# proiect-tsc.net
KiCad netlist of a schematic drawn in EAGLE
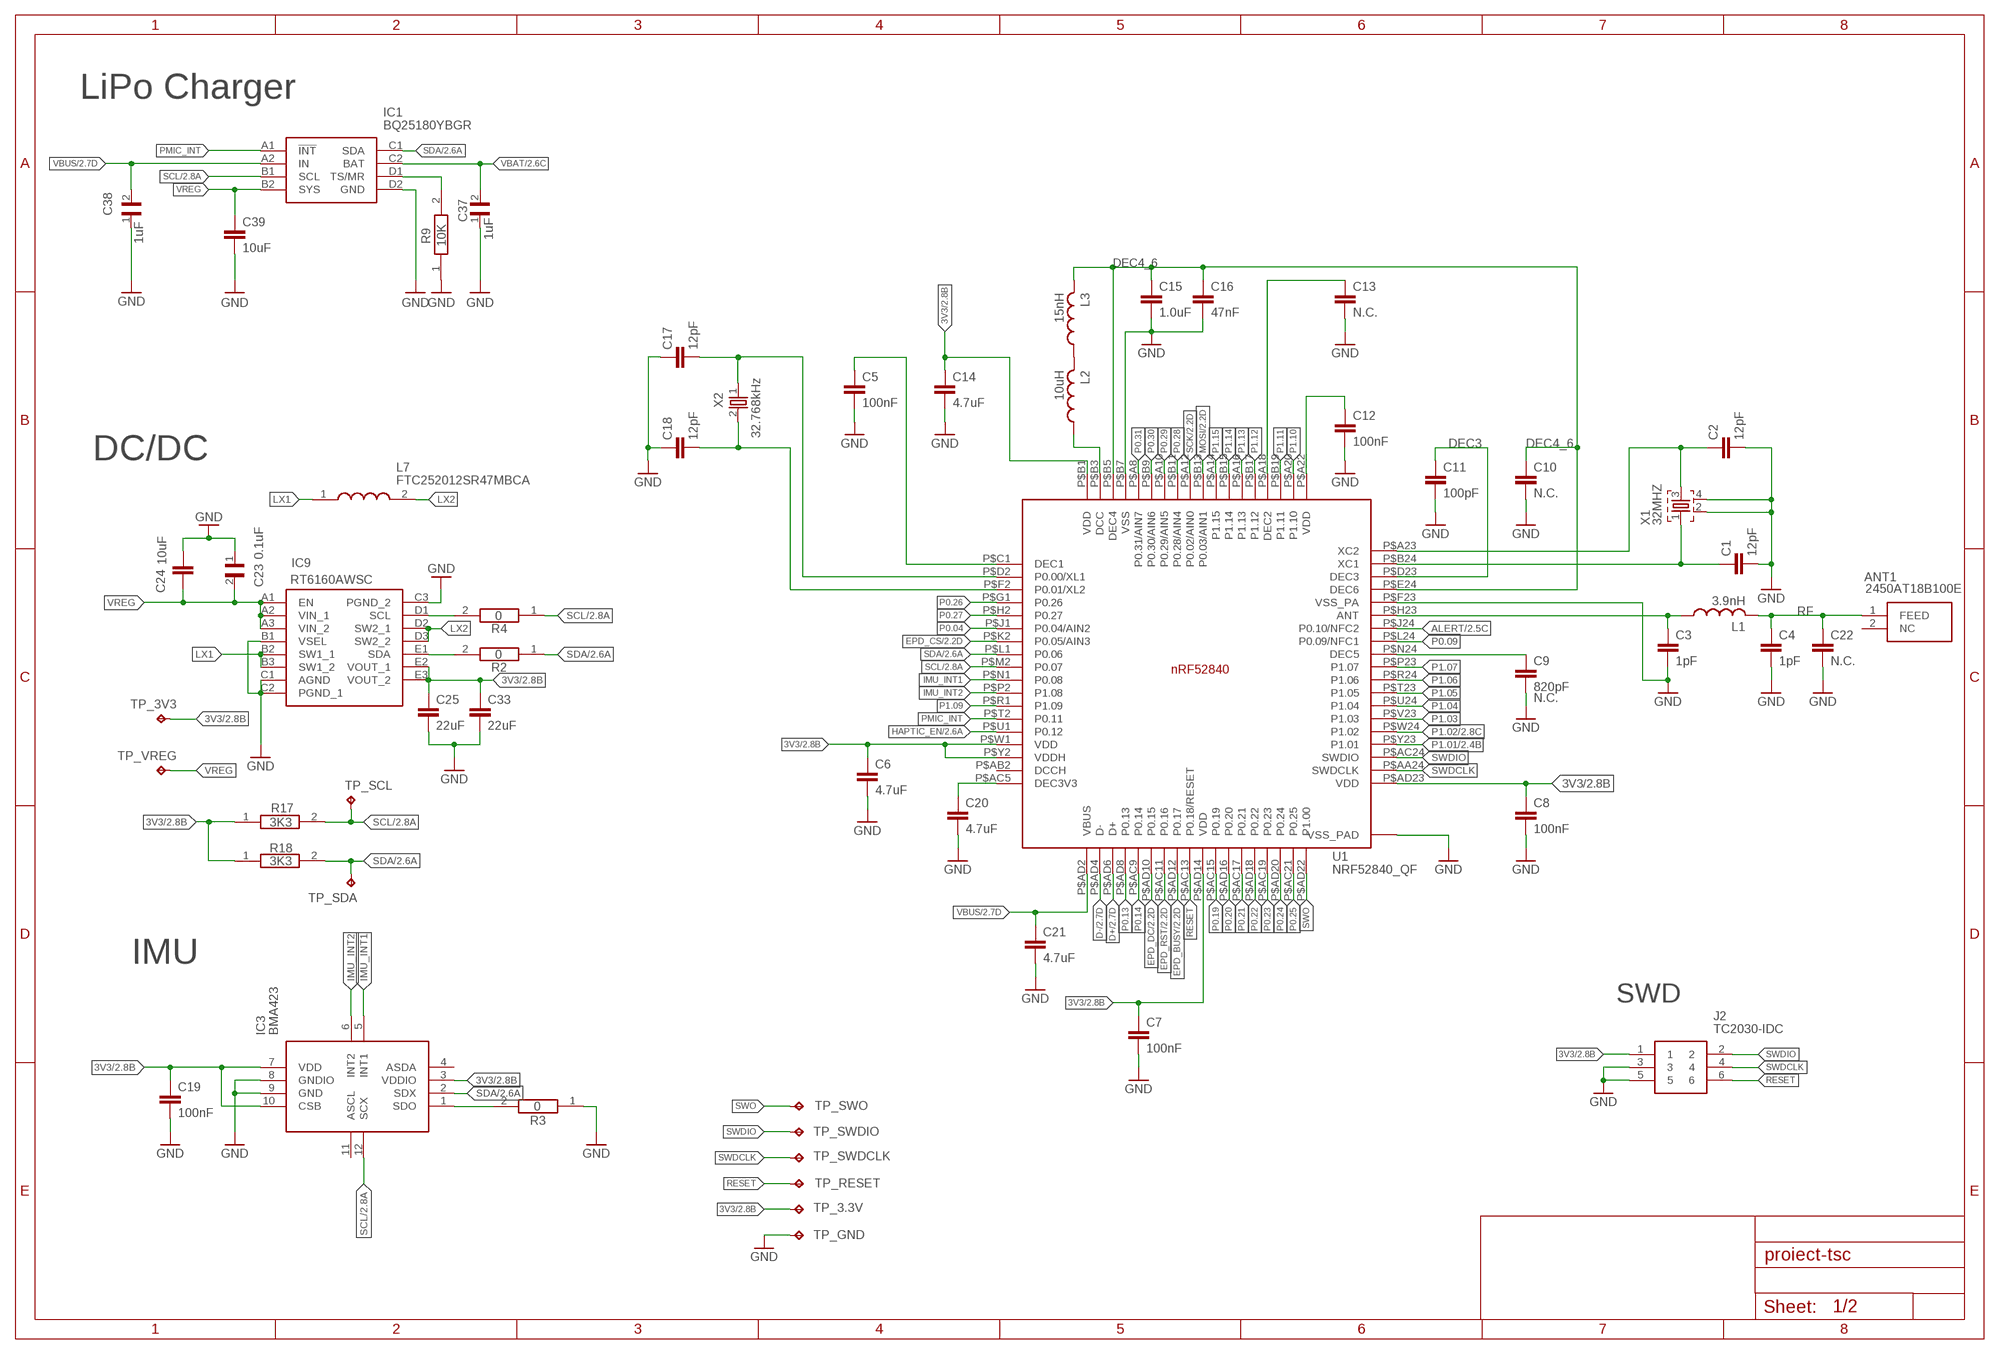
[diagram p0: schematic, sheet 1]
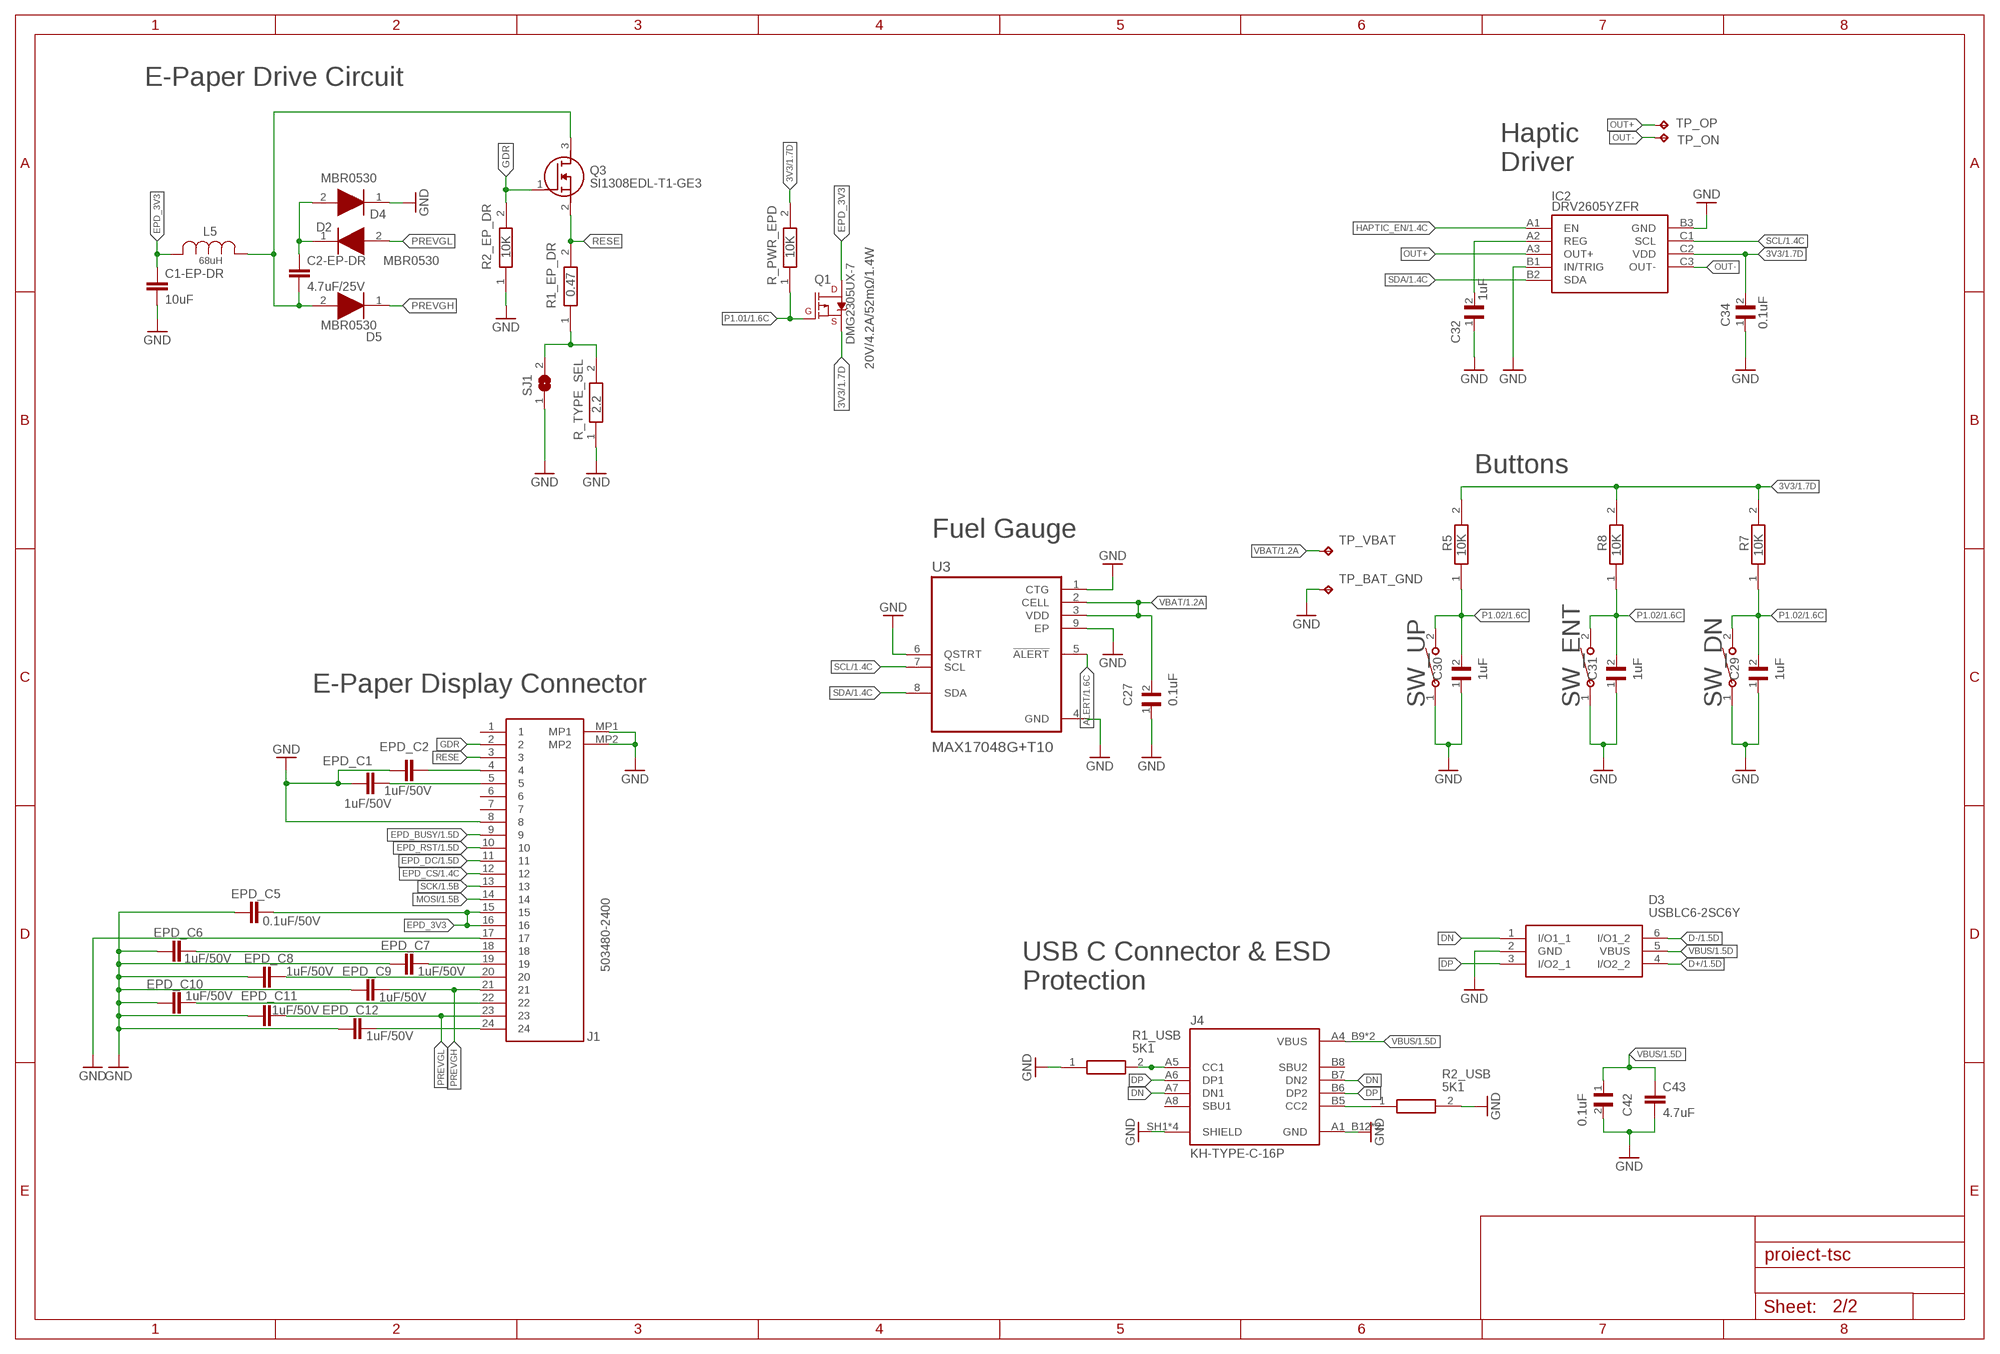
[diagram p1: schematic, sheet 2]

(export (version "E")
  (design (tool "Eeschema 10.0.6"))
  (components
    (comp (ref "C1-EP-DR")
      (value "10uF")
      (footprint "eagle-import:NORDIC_NRF_3_RESC0402_L")
      (libsource (lib "eagle-import") (part "NORDIC_NRF_3_CAPACITOR_0402_L"))
    )
    (comp (ref "C2-EP-DR")
      (value "4.7uF/25V")
      (footprint "eagle-import:NORDIC_NRF_3_RESC0402_L")
      (libsource (lib "eagle-import") (part "NORDIC_NRF_3_CAPACITOR_0402_L"))
    )
    (comp (ref "C27")
      (value "0.1uF")
      (footprint "eagle-import:GRM011R60J152KE01L_2_CAPC0201X13N")
      (fields (field (name "MF") "Murata") (field (name "MP") "GRM011R60J152KE01L"))
      (libsource (lib "eagle-import") (part "GRM011R60J152KE01L_2_GRM011R60J152KE01L"))
    )
    (comp (ref "C29")
      (value "1uF")
      (footprint "eagle-import:GRM011R60J152KE01L_1_0201")
      (libsource (lib "eagle-import") (part "GRM011R60J152KE01L_1_GRM011R60J152KE01L"))
    )
    (comp (ref "C30")
      (value "1uF")
      (footprint "eagle-import:GRM011R60J152KE01L_1_0201")
      (libsource (lib "eagle-import") (part "GRM011R60J152KE01L_1_GRM011R60J152KE01L"))
    )
    (comp (ref "C31")
      (value "1uF")
      (footprint "eagle-import:GRM011R60J152KE01L_1_0201")
      (libsource (lib "eagle-import") (part "GRM011R60J152KE01L_1_GRM011R60J152KE01L"))
    )
    (comp (ref "C32")
      (value "1uF")
      (footprint "eagle-import:GRM011R60J152KE01L_2_CAPC0201X13N")
      (fields (field (name "MF") "Murata") (field (name "MP") "GRM011R60J152KE01L"))
      (libsource (lib "eagle-import") (part "GRM011R60J152KE01L_2_GRM011R60J152KE01L"))
    )
    (comp (ref "C34")
      (value "0.1uF")
      (footprint "eagle-import:GRM011R60J152KE01L_2_CAPC0201X13N")
      (fields (field (name "MF") "Murata") (field (name "MP") "GRM011R60J152KE01L"))
      (libsource (lib "eagle-import") (part "GRM011R60J152KE01L_2_GRM011R60J152KE01L"))
    )
    (comp (ref "C42")
      (value "0.1uF")
      (footprint "eagle-import:GRM011R60J152KE01L_1_0201")
      (libsource (lib "eagle-import") (part "GRM011R60J152KE01L_1_GRM011R60J152KE01L"))
    )
    (comp (ref "C43")
      (value "4.7uF")
      (footprint "eagle-import:PERFECT_0402_0402")
      (libsource (lib "eagle-import") (part "PERFECT_0402_CAP_0402"))
    )
    (comp (ref "D2")
      (value "MBR0530")
      (footprint "eagle-import:ESP32_C6_LIBRARY_5_SOD3716X135N")
      (fields (field (name "MF") "ON Semiconductor"))
      (libsource (lib "eagle-import") (part "ESP32_C6_LIBRARY_5_MBR0530"))
    )
    (comp (ref "D3")
      (value "USBLC6-2SC6Y")
      (footprint "eagle-import:ESP32_C6_LIBRARY_3_SOT95P280X145-6N")
      (fields (field (name "MF") "STMicroelectronics"))
      (libsource (lib "eagle-import") (part "ESP32_C6_LIBRARY_3_USBLC6-2SC6Y"))
    )
    (comp (ref "D4")
      (value "MBR0530")
      (footprint "eagle-import:ESP32_C6_LIBRARY_5_SOD3716X135N")
      (fields (field (name "MF") "ON Semiconductor"))
      (libsource (lib "eagle-import") (part "ESP32_C6_LIBRARY_5_MBR0530"))
    )
    (comp (ref "D5")
      (value "MBR0530")
      (footprint "eagle-import:ESP32_C6_LIBRARY_5_SOD3716X135N")
      (fields (field (name "MF") "ON Semiconductor"))
      (libsource (lib "eagle-import") (part "ESP32_C6_LIBRARY_5_MBR0530"))
    )
    (comp (ref "EPD_C1")
      (value "1uF/50V")
      (footprint "eagle-import:NORDIC_NRF_3_RESC0402_L")
      (libsource (lib "eagle-import") (part "NORDIC_NRF_3_CAPACITOR_0402_L"))
    )
    (comp (ref "EPD_C2")
      (value "1uF/50V")
      (footprint "eagle-import:NORDIC_NRF_3_RESC0402_L")
      (libsource (lib "eagle-import") (part "NORDIC_NRF_3_CAPACITOR_0402_L"))
    )
    (comp (ref "EPD_C5")
      (value "0.1uF/50V")
      (footprint "eagle-import:NORDIC_NRF_3_RESC0402_L")
      (libsource (lib "eagle-import") (part "NORDIC_NRF_3_CAPACITOR_0402_L"))
    )
    (comp (ref "EPD_C6")
      (value "1uF/50V")
      (footprint "eagle-import:NORDIC_NRF_3_RESC0402_L")
      (libsource (lib "eagle-import") (part "NORDIC_NRF_3_CAPACITOR_0402_L"))
    )
    (comp (ref "EPD_C7")
      (value "1uF/50V")
      (footprint "eagle-import:NORDIC_NRF_3_RESC0402_L")
      (libsource (lib "eagle-import") (part "NORDIC_NRF_3_CAPACITOR_0402_L"))
    )
    (comp (ref "EPD_C8")
      (value "1uF/50V")
      (footprint "eagle-import:NORDIC_NRF_3_RESC0402_L")
      (libsource (lib "eagle-import") (part "NORDIC_NRF_3_CAPACITOR_0402_L"))
    )
    (comp (ref "EPD_C9")
      (value "1uF/50V")
      (footprint "eagle-import:NORDIC_NRF_3_RESC0402_L")
      (libsource (lib "eagle-import") (part "NORDIC_NRF_3_CAPACITOR_0402_L"))
    )
    (comp (ref "EPD_C10")
      (value "1uF/50V")
      (footprint "eagle-import:NORDIC_NRF_3_RESC0402_L")
      (libsource (lib "eagle-import") (part "NORDIC_NRF_3_CAPACITOR_0402_L"))
    )
    (comp (ref "EPD_C11")
      (value "1uF/50V")
      (footprint "eagle-import:NORDIC_NRF_3_RESC0402_L")
      (libsource (lib "eagle-import") (part "NORDIC_NRF_3_CAPACITOR_0402_L"))
    )
    (comp (ref "EPD_C12")
      (value "1uF/50V")
      (footprint "eagle-import:NORDIC_NRF_3_RESC0402_L")
      (libsource (lib "eagle-import") (part "NORDIC_NRF_3_CAPACITOR_0402_L"))
    )
    (comp (ref "IC2")
      (value "DRV2605YZFR")
      (footprint "eagle-import:DRV2605YZFR_BGA9C50P3X3_144X144X62")
      (libsource (lib "eagle-import") (part "DRV2605YZFR_DRV2605YZFR"))
    )
    (comp (ref "J1")
      (value "503480-2400")
      (footprint "eagle-import:503480-2400_5034802400")
      (fields (field (name "MOUSER_PART_NUMBER") "538-503480-2400"))
      (libsource (lib "eagle-import") (part "503480-2400_503480-2400"))
    )
    (comp (ref "J4")
      (value "KH-TYPE-C-16P")
      (footprint "eagle-import:KH-TYPE-C-16P_KINGHELM_KH-TYPE-C-16P")
      (fields (field (name "MF") "kinghelm"))
      (libsource (lib "eagle-import") (part "KH-TYPE-C-16P_KH-TYPE-C-16P"))
    )
    (comp (ref "L5")
      (value "68uH")
      (footprint "eagle-import:ESP32_C6_LIBRARY_2_IND_4828-WE-TPC_WRE")
      (fields
        (field (name "MANUFACTURER_PART_NUMBER") "744043680")
        (field (name "COPYRIGHT") "Copyright (C) 2024 Ultra Librarian. All rights reserved.")
      )
      (libsource (lib "eagle-import") (part "ESP32_C6_LIBRARY_2_744043680IND_4828-WE-TPC_WRE"))
    )
    (comp (ref "Q1")
      (value "20V/4.2A/52mΩ/1.4W")
      (footprint "eagle-import:ESP32_C6_LIBRARY_4_ESP32_C6_LIBRARY_4_ESP32_C6_LIBRARY_4_ESP32_C6_LIBRARY_4_ESP32_WROVER_SPARKFUN-DISCRETESEMI_SOT23-3")
      (libsource (lib "eagle-import") (part "ESP32_C6_LIBRARY_4_ESP32_WROVER_SPARKFUN-DISCRETESEMI_MOSFET_PCH-DMG2305UX-7"))
    )
    (comp (ref "Q3")
      (value "SI1308EDL-T1-GE3")
      (footprint "eagle-import:ESP32_C6_LIBRARY_6_SOT65P210X110-3N")
      (fields (field (name "MF") "Vishay Siliconix"))
      (libsource (lib "eagle-import") (part "ESP32_C6_LIBRARY_6_SI1308EDL-T1-GE3"))
    )
    (comp (ref "R1_EP_DR")
      (value "0.47")
      (footprint "eagle-import:CPF0201D7K68C1_0201")
      (libsource (lib "eagle-import") (part "CPF0201D7K68C1_CPF0201D7K68C1"))
    )
    (comp (ref "R1_USB")
      (value "5K1")
      (footprint "eagle-import:CPF0201D7K68C1_0201")
      (libsource (lib "eagle-import") (part "CPF0201D7K68C1_CPF0201D7K68C1"))
    )
    (comp (ref "R2_EP_DR")
      (value "10K")
      (footprint "eagle-import:CPF0201D7K68C1_0201")
      (libsource (lib "eagle-import") (part "CPF0201D7K68C1_CPF0201D7K68C1"))
    )
    (comp (ref "R2_USB")
      (value "5K1")
      (footprint "eagle-import:CPF0201D7K68C1_0201")
      (libsource (lib "eagle-import") (part "CPF0201D7K68C1_CPF0201D7K68C1"))
    )
    (comp (ref "R5")
      (value "10K")
      (footprint "eagle-import:CPF0201D7K68C1_0201")
      (libsource (lib "eagle-import") (part "CPF0201D7K68C1_CPF0201D7K68C1"))
    )
    (comp (ref "R7")
      (value "10K")
      (footprint "eagle-import:CPF0201D7K68C1_0201")
      (libsource (lib "eagle-import") (part "CPF0201D7K68C1_CPF0201D7K68C1"))
    )
    (comp (ref "R8")
      (value "10K")
      (footprint "eagle-import:CPF0201D7K68C1_0201")
      (libsource (lib "eagle-import") (part "CPF0201D7K68C1_CPF0201D7K68C1"))
    )
    (comp (ref "R_PWR_EPD")
      (value "10K")
      (footprint "eagle-import:CPF0201D7K68C1_0201")
      (libsource (lib "eagle-import") (part "CPF0201D7K68C1_CPF0201D7K68C1"))
    )
    (comp (ref "R_TYPE_SEL")
      (value "2.2")
      (footprint "eagle-import:CPF0201D7K68C1_0201")
      (libsource (lib "eagle-import") (part "CPF0201D7K68C1_CPF0201D7K68C1"))
    )
    (comp (ref "SJ1")
      (value "ESP32_C6_LIBRARY_7_JUMPER_SJ")
      (footprint "eagle-import:ESP32_C6_LIBRARY_7_JUMPER_SJ")
      (libsource (lib "eagle-import") (part "ESP32_C6_LIBRARY_7_JUMPER_SJ"))
    )
    (comp (ref "SW_DN")
      (value "2025-10-22_07-23-44_LIBRARY_EVP-AKE31ASW_EVP-AKE31A_PAN")
      (footprint "eagle-import:2025-10-22_07-23-44_LIBRARY_SW_EVP-AKE31A_PAN")
      (fields
        (field (name "MANUFACTURER_PART_NUMBER") "EVP-AKE31A")
        (field (name "COPYRIGHT") "Copyright (C) 2025 Ultra Librarian. All rights reserved.")
      )
      (libsource (lib "eagle-import") (part "2025-10-22_07-23-44_LIBRARY_EVP-AKE31ASW_EVP-AKE31A_PAN"))
    )
    (comp (ref "SW_ENT")
      (value "2025-10-22_07-23-44_LIBRARY_EVP-AKE31ASW_EVP-AKE31A_PAN")
      (footprint "eagle-import:2025-10-22_07-23-44_LIBRARY_SW_EVP-AKE31A_PAN")
      (fields
        (field (name "MANUFACTURER_PART_NUMBER") "EVP-AKE31A")
        (field (name "COPYRIGHT") "Copyright (C) 2025 Ultra Librarian. All rights reserved.")
      )
      (libsource (lib "eagle-import") (part "2025-10-22_07-23-44_LIBRARY_EVP-AKE31ASW_EVP-AKE31A_PAN"))
    )
    (comp (ref "SW_UP")
      (value "2025-10-22_07-23-44_LIBRARY_EVP-AKE31ASW_EVP-AKE31A_PAN")
      (footprint "eagle-import:2025-10-22_07-23-44_LIBRARY_SW_EVP-AKE31A_PAN")
      (fields
        (field (name "MANUFACTURER_PART_NUMBER") "EVP-AKE31A")
        (field (name "COPYRIGHT") "Copyright (C) 2025 Ultra Librarian. All rights reserved.")
      )
      (libsource (lib "eagle-import") (part "2025-10-22_07-23-44_LIBRARY_EVP-AKE31ASW_EVP-AKE31A_PAN"))
    )
    (comp (ref "TP_BAT_GND")
      (value "HECTOR_WATCH_1_TPTP20R")
      (footprint "eagle-import:HECTOR_WATCH_1_TP20R")
      (libsource (lib "eagle-import") (part "HECTOR_WATCH_1_TPTP20R"))
    )
    (comp (ref "TP_ON")
      (value "HECTOR_WATCH_1_TPTP20R")
      (footprint "eagle-import:HECTOR_WATCH_1_TP20R")
      (libsource (lib "eagle-import") (part "HECTOR_WATCH_1_TPTP20R"))
    )
    (comp (ref "TP_OP")
      (value "HECTOR_WATCH_1_TPTP20R")
      (footprint "eagle-import:HECTOR_WATCH_1_TP20R")
      (libsource (lib "eagle-import") (part "HECTOR_WATCH_1_TPTP20R"))
    )
    (comp (ref "TP_VBAT")
      (value "HECTOR_WATCH_1_TPTP20R")
      (footprint "eagle-import:HECTOR_WATCH_1_TP20R")
      (libsource (lib "eagle-import") (part "HECTOR_WATCH_1_TPTP20R"))
    )
    (comp (ref "U3")
      (value "MAX17048G+T10")
      (footprint "eagle-import:ESP32_C6_LIBRARY_SON50P200X200X80-9N")
      (fields (field (name "MF") "Analog Devices"))
      (libsource (lib "eagle-import") (part "ESP32_C6_LIBRARY_MAX17048G+T10"))
    )
    (comp (ref "ANT1")
      (value "2450AT18B100E")
      (footprint "eagle-import:2450AT18B100E_ANTC3216X140N")
      (fields (field (name "MOUSER_PART_NUMBER") "609-2450AT18B100E"))
      (libsource (lib "eagle-import") (part "2450AT18B100E_2450AT18B100E"))
    )
    (comp (ref "C1")
      (value "12pF")
      (footprint "eagle-import:NORDIC_NRF_3_RESC0201_L")
      (libsource (lib "eagle-import") (part "NORDIC_NRF_3_CAPACITOR_0201_L"))
    )
    (comp (ref "C2")
      (value "12pF")
      (footprint "eagle-import:NORDIC_NRF_3_RESC0201_L")
      (libsource (lib "eagle-import") (part "NORDIC_NRF_3_CAPACITOR_0201_L"))
    )
    (comp (ref "C3")
      (value "1pF")
      (footprint "eagle-import:NORDIC_NRF_3_RESC0201_L")
      (libsource (lib "eagle-import") (part "NORDIC_NRF_3_CAPACITOR_0201_L"))
    )
    (comp (ref "C4")
      (value "1pF")
      (footprint "eagle-import:NORDIC_NRF_3_RESC0201_L")
      (libsource (lib "eagle-import") (part "NORDIC_NRF_3_CAPACITOR_0201_L"))
    )
    (comp (ref "C5")
      (value "100nF")
      (footprint "eagle-import:NORDIC_NRF_3_RESC0201_L")
      (libsource (lib "eagle-import") (part "NORDIC_NRF_3_CAPACITOR_0201_L"))
    )
    (comp (ref "C6")
      (value "4.7uF")
      (footprint "eagle-import:NORDIC_NRF_3_RESC0402_L")
      (libsource (lib "eagle-import") (part "NORDIC_NRF_3_CAPACITOR_0402_L"))
    )
    (comp (ref "C7")
      (value "100nF")
      (footprint "eagle-import:NORDIC_NRF_3_RESC0201_L")
      (libsource (lib "eagle-import") (part "NORDIC_NRF_3_CAPACITOR_0201_L"))
    )
    (comp (ref "C8")
      (value "100nF")
      (footprint "eagle-import:NORDIC_NRF_3_RESC0201_L")
      (libsource (lib "eagle-import") (part "NORDIC_NRF_3_CAPACITOR_0201_L"))
    )
    (comp (ref "C9")
      (value "820pF")
      (footprint "eagle-import:NORDIC_NRF_3_RESC0201_L")
      (libsource (lib "eagle-import") (part "NORDIC_NRF_3_CAPACITOR_0201_L"))
    )
    (comp (ref "C10")
      (value "N.C.")
      (footprint "eagle-import:NORDIC_NRF_3_RESC0201_L")
      (libsource (lib "eagle-import") (part "NORDIC_NRF_3_CAPACITOR_0201_L"))
    )
    (comp (ref "C11")
      (value "100pF")
      (footprint "eagle-import:NORDIC_NRF_3_RESC0201_L")
      (libsource (lib "eagle-import") (part "NORDIC_NRF_3_CAPACITOR_0201_L"))
    )
    (comp (ref "C12")
      (value "100nF")
      (footprint "eagle-import:NORDIC_NRF_3_RESC0201_L")
      (libsource (lib "eagle-import") (part "NORDIC_NRF_3_CAPACITOR_0201_L"))
    )
    (comp (ref "C13")
      (value "N.C.")
      (footprint "eagle-import:NORDIC_NRF_3_RESC0201_L")
      (libsource (lib "eagle-import") (part "NORDIC_NRF_3_CAPACITOR_0201_L"))
    )
    (comp (ref "C14")
      (value "4.7uF")
      (footprint "eagle-import:NORDIC_NRF_3_RESC0201_L")
      (libsource (lib "eagle-import") (part "NORDIC_NRF_3_CAPACITOR_0201_L"))
    )
    (comp (ref "C15")
      (value "1.0uF")
      (footprint "eagle-import:NORDIC_NRF_3_RESC0201_L")
      (libsource (lib "eagle-import") (part "NORDIC_NRF_3_CAPACITOR_0201_L"))
    )
    (comp (ref "C16")
      (value "47nF")
      (footprint "eagle-import:NORDIC_NRF_3_RESC0201_L")
      (libsource (lib "eagle-import") (part "NORDIC_NRF_3_CAPACITOR_0201_L"))
    )
    (comp (ref "C17")
      (value "12pF")
      (footprint "eagle-import:PERFECT_0402_0402")
      (libsource (lib "eagle-import") (part "PERFECT_0402_CAP_0402"))
    )
    (comp (ref "C18")
      (value "12pF")
      (footprint "eagle-import:PERFECT_0402_0402")
      (libsource (lib "eagle-import") (part "PERFECT_0402_CAP_0402"))
    )
    (comp (ref "C19")
      (value "100nF")
      (footprint "eagle-import:PERFECT_0402_0402")
      (libsource (lib "eagle-import") (part "PERFECT_0402_CAP_0402"))
    )
    (comp (ref "C20")
      (value "4.7uF")
      (footprint "eagle-import:NORDIC_NRF_3_RESC0402_L")
      (libsource (lib "eagle-import") (part "NORDIC_NRF_3_CAPACITOR_0402_L"))
    )
    (comp (ref "C21")
      (value "4.7uF")
      (footprint "eagle-import:NORDIC_NRF_3_RESC0402_L")
      (libsource (lib "eagle-import") (part "NORDIC_NRF_3_CAPACITOR_0402_L"))
    )
    (comp (ref "C22")
      (value "N.C.")
      (footprint "eagle-import:NORDIC_NRF_3_RESC0201_L")
      (libsource (lib "eagle-import") (part "NORDIC_NRF_3_CAPACITOR_0201_L"))
    )
    (comp (ref "C23")
      (value "0.1uF")
      (footprint "eagle-import:GRM011R60J152KE01L_2_CAPC0201X13N")
      (fields (field (name "MF") "Murata") (field (name "MP") "GRM011R60J152KE01L"))
      (libsource (lib "eagle-import") (part "GRM011R60J152KE01L_2_GRM011R60J152KE01L"))
    )
    (comp (ref "C24")
      (value "10uF")
      (footprint "eagle-import:PERFECT_0402_0402")
      (libsource (lib "eagle-import") (part "PERFECT_0402_CAP_0402"))
    )
    (comp (ref "C25")
      (value "22uF")
      (footprint "eagle-import:PERFECT_0402_0402")
      (libsource (lib "eagle-import") (part "PERFECT_0402_CAP_0402"))
    )
    (comp (ref "C33")
      (value "22uF")
      (footprint "eagle-import:PERFECT_0402_0402")
      (libsource (lib "eagle-import") (part "PERFECT_0402_CAP_0402"))
    )
    (comp (ref "C37")
      (value "1uF")
      (footprint "eagle-import:GRM011R60J152KE01L_2_CAPC0201X13N")
      (fields (field (name "MF") "Murata") (field (name "MP") "GRM011R60J152KE01L"))
      (libsource (lib "eagle-import") (part "GRM011R60J152KE01L_2_GRM011R60J152KE01L"))
    )
    (comp (ref "C38")
      (value "1uF")
      (footprint "eagle-import:GRM011R60J152KE01L_2_CAPC0201X13N")
      (fields (field (name "MF") "Murata") (field (name "MP") "GRM011R60J152KE01L"))
      (libsource (lib "eagle-import") (part "GRM011R60J152KE01L_2_GRM011R60J152KE01L"))
    )
    (comp (ref "C39")
      (value "10uF")
      (footprint "eagle-import:PERFECT_0402_0402")
      (libsource (lib "eagle-import") (part "PERFECT_0402_CAP_0402"))
    )
    (comp (ref "IC1")
      (value "BQ25180YBGR")
      (footprint "eagle-import:BQ25180YBGR_BGA8C40P2X4_100X155X50")
      (fields (field (name "MOUSER_PART_NUMBER") "595-BQ25180YBGR"))
      (libsource (lib "eagle-import") (part "BQ25180YBGR_BQ25180YBGR"))
    )
    (comp (ref "IC3")
      (value "BMA423")
      (footprint "eagle-import:BMA423_BMA423")
      (fields (field (name "MOUSER_PART_NUMBER") "262-BMA423"))
      (libsource (lib "eagle-import") (part "BMA423_BMA423"))
    )
    (comp (ref "IC9")
      (value "RT6160AWSC")
      (footprint "eagle-import:RT6160AWSC_BGA15C40P3X5_140X230X60")
      (fields (field (name "MOUSER_PART_NUMBER") "835-RT6160AWSC"))
      (libsource (lib "eagle-import") (part "RT6160AWSC_RT6160AWSC"))
    )
    (comp (ref "J2")
      (value "TC2030-IDC")
      (footprint "eagle-import:TC2030-IDC_TC2030IDC")
      (libsource (lib "eagle-import") (part "TC2030-IDC_TC2030-IDC"))
    )
    (comp (ref "L1")
      (value "3.9nH")
      (footprint "eagle-import:NORDIC_NRF_2_RESC0201_L")
      (libsource (lib "eagle-import") (part "NORDIC_NRF_2_INDUCTOR_0201_L"))
    )
    (comp (ref "L2")
      (value "10uH")
      (footprint "eagle-import:NORDIC_NRF_2_RESC0402_L")
      (libsource (lib "eagle-import") (part "NORDIC_NRF_2_INDUCTOR_0402_L"))
    )
    (comp (ref "L3")
      (value "15nH")
      (footprint "eagle-import:NORDIC_NRF_2_RESC0402_L")
      (libsource (lib "eagle-import") (part "NORDIC_NRF_2_INDUCTOR_0402_L"))
    )
    (comp (ref "L7")
      (value "FTC252012SR47MBCA")
      (footprint "eagle-import:MLP2016SR47MT0S1_INDC2016X100N")
      (libsource (lib "eagle-import") (part "MLP2016SR47MT0S1_FTC252012SR47MBCA"))
    )
    (comp (ref "R2")
      (value "0")
      (footprint "eagle-import:ERA-1AEB3401C_0201")
      (libsource (lib "eagle-import") (part "ERA-1AEB3401C_CPF0201D7K68C1"))
    )
    (comp (ref "R3")
      (value "0")
      (footprint "eagle-import:CPF0201D7K68C1_0201")
      (libsource (lib "eagle-import") (part "CPF0201D7K68C1_CPF0201D7K68C1"))
    )
    (comp (ref "R4")
      (value "0")
      (footprint "eagle-import:ERA-1AEB3401C_0201")
      (libsource (lib "eagle-import") (part "ERA-1AEB3401C_CPF0201D7K68C1"))
    )
    (comp (ref "R9")
      (value "10K")
      (footprint "eagle-import:CPF0201D7K68C1_0201")
      (libsource (lib "eagle-import") (part "CPF0201D7K68C1_CPF0201D7K68C1"))
    )
    (comp (ref "R17")
      (value "3K3")
      (footprint "eagle-import:CPF0201D7K68C1_0201")
      (libsource (lib "eagle-import") (part "CPF0201D7K68C1_CPF0201D7K68C1"))
    )
    (comp (ref "R18")
      (value "3K3")
      (footprint "eagle-import:CPF0201D7K68C1_0201")
      (libsource (lib "eagle-import") (part "CPF0201D7K68C1_CPF0201D7K68C1"))
    )
    (comp (ref "TP_3.3V")
      (value "HECTOR_WATCH_1_TPTP20R")
      (footprint "eagle-import:HECTOR_WATCH_1_TP20R")
      (libsource (lib "eagle-import") (part "HECTOR_WATCH_1_TPTP20R"))
    )
    (comp (ref "TP_3V3")
      (value "HECTOR_WATCH_1_TPTP20R")
      (footprint "eagle-import:HECTOR_WATCH_1_TP20R")
      (libsource (lib "eagle-import") (part "HECTOR_WATCH_1_TPTP20R"))
    )
    (comp (ref "TP_GND")
      (value "HECTOR_WATCH_1_TPTP20R")
      (footprint "eagle-import:HECTOR_WATCH_1_TP20R")
      (libsource (lib "eagle-import") (part "HECTOR_WATCH_1_TPTP20R"))
    )
    (comp (ref "TP_RESET")
      (value "HECTOR_WATCH_1_TPTP20R")
      (footprint "eagle-import:HECTOR_WATCH_1_TP20R")
      (libsource (lib "eagle-import") (part "HECTOR_WATCH_1_TPTP20R"))
    )
    (comp (ref "TP_SCL")
      (value "HECTOR_WATCH_1_TPTP20R")
      (footprint "eagle-import:HECTOR_WATCH_1_TP20R")
      (libsource (lib "eagle-import") (part "HECTOR_WATCH_1_TPTP20R"))
    )
    (comp (ref "TP_SDA")
      (value "HECTOR_WATCH_1_TPTP20R")
      (footprint "eagle-import:HECTOR_WATCH_1_TP20R")
      (libsource (lib "eagle-import") (part "HECTOR_WATCH_1_TPTP20R"))
    )
    (comp (ref "TP_SWDCLK")
      (value "HECTOR_WATCH_1_TPTP20R")
      (footprint "eagle-import:HECTOR_WATCH_1_TP20R")
      (libsource (lib "eagle-import") (part "HECTOR_WATCH_1_TPTP20R"))
    )
    (comp (ref "TP_SWDIO")
      (value "HECTOR_WATCH_1_TPTP20R")
      (footprint "eagle-import:HECTOR_WATCH_1_TP20R")
      (libsource (lib "eagle-import") (part "HECTOR_WATCH_1_TPTP20R"))
    )
    (comp (ref "TP_SWO")
      (value "HECTOR_WATCH_1_TPTP20R")
      (footprint "eagle-import:HECTOR_WATCH_1_TP20R")
      (libsource (lib "eagle-import") (part "HECTOR_WATCH_1_TPTP20R"))
    )
    (comp (ref "TP_VREG")
      (value "HECTOR_WATCH_1_TPTP20R")
      (footprint "eagle-import:HECTOR_WATCH_1_TP20R")
      (libsource (lib "eagle-import") (part "HECTOR_WATCH_1_TPTP20R"))
    )
    (comp (ref "U1")
      (value "NRF52840_QF")
      (footprint "eagle-import:NORDIC_NRF_4_AQFN50P700X700X85_HS-74N")
      (libsource (lib "eagle-import") (part "NORDIC_NRF_4_NRF52840_QF"))
    )
    (comp (ref "X1")
      (value "32MHZ")
      (footprint "eagle-import:NORDIC_NRF_BT-XTAL_2016_N")
      (libsource (lib "eagle-import") (part "NORDIC_NRF_XTAL_32MHZ"))
    )
    (comp (ref "X2")
      (value "32.768kHz")
      (footprint "eagle-import:NORDIC_NRF_1_XTAL_3215_N")
      (libsource (lib "eagle-import") (part "NORDIC_NRF_1_XTAL_32KHZ"))
    )
  )
  (nets
    (net (code "1") (name "3V3") (class "Default")
      (node (ref "C14") (pin "1") (pinfunction "1_1") (pintype "passive"))
      (node (ref "C19") (pin "1") (pinfunction "1_1") (pintype "passive"))
      (node (ref "C25") (pin "1") (pinfunction "1_1") (pintype "passive"))
      (node (ref "C33") (pin "1") (pinfunction "1_1") (pintype "passive"))
      (node (ref "C34") (pin "2") (pinfunction "2_2") (pintype "passive"))
      (node (ref "C6") (pin "1") (pinfunction "1_1") (pintype "passive"))
      (node (ref "C7") (pin "1") (pinfunction "1_1") (pintype "passive"))
      (node (ref "C8") (pin "1") (pinfunction "1_1") (pintype "passive"))
      (node (ref "IC2") (pin "C2") (pinfunction "VDD_C2") (pintype "bidirectional"))
      (node (ref "IC3") (pin "10") (pinfunction "CSB_10") (pintype "bidirectional"))
      (node (ref "IC3") (pin "3") (pinfunction "VDDIO_3") (pintype "bidirectional"))
      (node (ref "IC3") (pin "7") (pinfunction "VDD_7") (pintype "bidirectional"))
      (node (ref "IC9") (pin "E2") (pinfunction "VOUT_1_E2") (pintype "bidirectional"))
      (node (ref "IC9") (pin "E3") (pinfunction "VOUT_2_E3") (pintype "bidirectional"))
      (node (ref "J2") (pin "1") (pinfunction "1_1") (pintype "bidirectional"))
      (node (ref "Q1") (pin "2") (pinfunction "S_2") (pintype "bidirectional"))
      (node (ref "R17") (pin "1") (pinfunction "1_1") (pintype "bidirectional"))
      (node (ref "R18") (pin "1") (pinfunction "1_1") (pintype "bidirectional"))
      (node (ref "R5") (pin "2") (pinfunction "2_2") (pintype "bidirectional"))
      (node (ref "R7") (pin "2") (pinfunction "2_2") (pintype "bidirectional"))
      (node (ref "R8") (pin "2") (pinfunction "2_2") (pintype "bidirectional"))
      (node (ref "R_PWR_EPD") (pin "2") (pinfunction "2_2") (pintype "bidirectional"))
      (node (ref "TP_3.3V") (pin "TP") (pinfunction "TP_TP") (pintype "input"))
      (node (ref "TP_3V3") (pin "TP") (pinfunction "TP_TP") (pintype "input"))
      (node (ref "U1") (pin "P$AD14") (pinfunction "VDD_P$AD14") (pintype "power_in"))
      (node (ref "U1") (pin "P$AD23") (pinfunction "VDD_P$AD23") (pintype "power_in"))
      (node (ref "U1") (pin "P$B1") (pinfunction "VDD_P$B1") (pintype "power_in"))
      (node (ref "U1") (pin "P$W1") (pinfunction "VDD_P$W1") (pintype "power_in"))
      (node (ref "U1") (pin "P$Y2") (pinfunction "VDDH_P$Y2") (pintype "power_in"))
    )
    (net (code "2") (name "ALERT") (class "Default")
      (node (ref "U1") (pin "P$J24") (pinfunction "P0.10/NFC2_P$J24") (pintype "bidirectional"))
      (node (ref "U3") (pin "5") (pinfunction "~{ALERT}_5") (pintype "output"))
    )
    (net (code "3") (name "D+") (class "Default")
      (node (ref "D3") (pin "4") (pinfunction "I/O2_2_4") (pintype "bidirectional"))
      (node (ref "U1") (pin "P$AD6") (pinfunction "D+_P$AD6") (pintype "bidirectional"))
    )
    (net (code "4") (name "D-") (class "Default")
      (node (ref "D3") (pin "6") (pinfunction "I/O1_2_6") (pintype "bidirectional"))
      (node (ref "U1") (pin "P$AD4") (pinfunction "D-_P$AD4") (pintype "bidirectional"))
    )
    (net (code "5") (name "DEC4_6") (class "Default")
      (node (ref "C10") (pin "1") (pinfunction "1_1") (pintype "passive"))
      (node (ref "C15") (pin "1") (pinfunction "1_1") (pintype "passive"))
      (node (ref "C16") (pin "1") (pinfunction "1_1") (pintype "passive"))
      (node (ref "L3") (pin "2") (pinfunction "2_2") (pintype "passive"))
      (node (ref "U1") (pin "P$B5") (pinfunction "DEC4_P$B5") (pintype "power_in"))
      (node (ref "U1") (pin "P$E24") (pinfunction "DEC6_P$E24") (pintype "bidirectional"))
    )
    (net (code "6") (name "DN") (class "Default")
      (node (ref "D3") (pin "1") (pinfunction "I/O1_1_1") (pintype "bidirectional"))
      (node (ref "J4") (pin "A7") (pinfunction "DN1_A7") (pintype "bidirectional"))
      (node (ref "J4") (pin "B7") (pinfunction "DN2_B7") (pintype "bidirectional"))
    )
    (net (code "7") (name "DP") (class "Default")
      (node (ref "D3") (pin "3") (pinfunction "I/O2_1_3") (pintype "bidirectional"))
      (node (ref "J4") (pin "A6") (pinfunction "DP1_A6") (pintype "bidirectional"))
      (node (ref "J4") (pin "B6") (pinfunction "DP2_B6") (pintype "bidirectional"))
    )
    (net (code "8") (name "EPD_3V3") (class "Default")
      (node (ref "C1-EP-DR") (pin "1") (pinfunction "1_1") (pintype "passive"))
      (node (ref "EPD_C5") (pin "2") (pinfunction "2_2") (pintype "passive"))
      (node (ref "J1") (pin "15") (pinfunction "15_15") (pintype "bidirectional"))
      (node (ref "J1") (pin "16") (pinfunction "16_16") (pintype "bidirectional"))
      (node (ref "L5") (pin "2") (pinfunction "2_2") (pintype "passive"))
      (node (ref "Q1") (pin "3") (pinfunction "D_3") (pintype "bidirectional"))
    )
    (net (code "9") (name "EPD_BUSY") (class "Default")
      (node (ref "J1") (pin "9") (pinfunction "9_9") (pintype "bidirectional"))
      (node (ref "U1") (pin "P$AD12") (pinfunction "P0.17_P$AD12") (pintype "bidirectional"))
    )
    (net (code "10") (name "EPD_CS") (class "Default")
      (node (ref "J1") (pin "12") (pinfunction "12_12") (pintype "bidirectional"))
      (node (ref "U1") (pin "P$K2") (pinfunction "P0.05/AIN3_P$K2") (pintype "bidirectional"))
    )
    (net (code "11") (name "EPD_DC") (class "Default")
      (node (ref "J1") (pin "11") (pinfunction "11_11") (pintype "bidirectional"))
      (node (ref "U1") (pin "P$AD10") (pinfunction "P0.15_P$AD10") (pintype "bidirectional"))
    )
    (net (code "12") (name "EPD_RST") (class "Default")
      (node (ref "J1") (pin "10") (pinfunction "10_10") (pintype "bidirectional"))
      (node (ref "U1") (pin "P$AC11") (pinfunction "P0.16_P$AC11") (pintype "bidirectional"))
    )
    (net (code "13") (name "GDR") (class "Default")
      (node (ref "J1") (pin "2") (pinfunction "2_2") (pintype "bidirectional"))
      (node (ref "Q3") (pin "1") (pinfunction "G_1") (pintype "bidirectional"))
      (node (ref "R2_EP_DR") (pin "2") (pinfunction "2_2") (pintype "bidirectional"))
    )
    (net (code "14") (name "GND") (class "Default")
      (node (ref "C1") (pin "2") (pinfunction "2_2") (pintype "passive"))
      (node (ref "C1-EP-DR") (pin "2") (pinfunction "2_2") (pintype "passive"))
      (node (ref "C10") (pin "2") (pinfunction "2_2") (pintype "passive"))
      (node (ref "C11") (pin "2") (pinfunction "2_2") (pintype "passive"))
      (node (ref "C12") (pin "2") (pinfunction "2_2") (pintype "passive"))
      (node (ref "C13") (pin "2") (pinfunction "2_2") (pintype "passive"))
      (node (ref "C14") (pin "2") (pinfunction "2_2") (pintype "passive"))
      (node (ref "C15") (pin "2") (pinfunction "2_2") (pintype "passive"))
      (node (ref "C16") (pin "2") (pinfunction "2_2") (pintype "passive"))
      (node (ref "C17") (pin "1") (pinfunction "1_1") (pintype "passive"))
      (node (ref "C18") (pin "1") (pinfunction "1_1") (pintype "passive"))
      (node (ref "C19") (pin "2") (pinfunction "2_2") (pintype "passive"))
      (node (ref "C2") (pin "2") (pinfunction "2_2") (pintype "passive"))
      (node (ref "C20") (pin "2") (pinfunction "2_2") (pintype "passive"))
      (node (ref "C21") (pin "2") (pinfunction "2_2") (pintype "passive"))
      (node (ref "C22") (pin "2") (pinfunction "2_2") (pintype "passive"))
      (node (ref "C23") (pin "1") (pinfunction "1_1") (pintype "passive"))
      (node (ref "C24") (pin "1") (pinfunction "1_1") (pintype "passive"))
      (node (ref "C25") (pin "2") (pinfunction "2_2") (pintype "passive"))
      (node (ref "C27") (pin "1") (pinfunction "1_1") (pintype "passive"))
      (node (ref "C29") (pin "1") (pinfunction "1_1") (pintype "passive"))
      (node (ref "C3") (pin "2") (pinfunction "2_2") (pintype "passive"))
      (node (ref "C30") (pin "1") (pinfunction "1_1") (pintype "passive"))
      (node (ref "C31") (pin "1") (pinfunction "1_1") (pintype "passive"))
      (node (ref "C32") (pin "1") (pinfunction "1_1") (pintype "passive"))
      (node (ref "C33") (pin "2") (pinfunction "2_2") (pintype "passive"))
      (node (ref "C34") (pin "1") (pinfunction "1_1") (pintype "passive"))
      (node (ref "C37") (pin "1") (pinfunction "1_1") (pintype "passive"))
      (node (ref "C38") (pin "1") (pinfunction "1_1") (pintype "passive"))
      (node (ref "C39") (pin "2") (pinfunction "2_2") (pintype "passive"))
      (node (ref "C4") (pin "2") (pinfunction "2_2") (pintype "passive"))
      (node (ref "C42") (pin "2") (pinfunction "2_2") (pintype "passive"))
      (node (ref "C43") (pin "2") (pinfunction "2_2") (pintype "passive"))
      (node (ref "C5") (pin "2") (pinfunction "2_2") (pintype "passive"))
      (node (ref "C6") (pin "2") (pinfunction "2_2") (pintype "passive"))
      (node (ref "C7") (pin "2") (pinfunction "2_2") (pintype "passive"))
      (node (ref "C8") (pin "2") (pinfunction "2_2") (pintype "passive"))
      (node (ref "C9") (pin "2") (pinfunction "2_2") (pintype "passive"))
      (node (ref "D3") (pin "2") (pinfunction "GND_2") (pintype "bidirectional"))
      (node (ref "D4") (pin "1") (pinfunction "K_1") (pintype "bidirectional"))
      (node (ref "EPD_C1") (pin "1") (pinfunction "1_1") (pintype "passive"))
      (node (ref "EPD_C10") (pin "1") (pinfunction "1_1") (pintype "passive"))
      (node (ref "EPD_C11") (pin "1") (pinfunction "1_1") (pintype "passive"))
      (node (ref "EPD_C12") (pin "1") (pinfunction "1_1") (pintype "passive"))
      (node (ref "EPD_C2") (pin "1") (pinfunction "1_1") (pintype "passive"))
      (node (ref "EPD_C5") (pin "1") (pinfunction "1_1") (pintype "passive"))
      (node (ref "EPD_C6") (pin "1") (pinfunction "1_1") (pintype "passive"))
      (node (ref "EPD_C7") (pin "1") (pinfunction "1_1") (pintype "passive"))
      (node (ref "EPD_C8") (pin "1") (pinfunction "1_1") (pintype "passive"))
      (node (ref "EPD_C9") (pin "1") (pinfunction "1_1") (pintype "passive"))
      (node (ref "IC1") (pin "D2") (pinfunction "GND_D2") (pintype "bidirectional"))
      (node (ref "IC2") (pin "B1") (pinfunction "IN/TRIG_B1") (pintype "bidirectional"))
      (node (ref "IC2") (pin "B3") (pinfunction "GND_B3") (pintype "bidirectional"))
      (node (ref "IC3") (pin "8") (pinfunction "GNDIO_8") (pintype "bidirectional"))
      (node (ref "IC3") (pin "9") (pinfunction "GND_9") (pintype "bidirectional"))
      (node (ref "IC9") (pin "B1") (pinfunction "VSEL_B1") (pintype "bidirectional"))
      (node (ref "IC9") (pin "C1") (pinfunction "AGND_C1") (pintype "bidirectional"))
      (node (ref "IC9") (pin "C2") (pinfunction "PGND_1_C2") (pintype "bidirectional"))
      (node (ref "IC9") (pin "C3") (pinfunction "PGND_2_C3") (pintype "bidirectional"))
      (node (ref "J1") (pin "17") (pinfunction "17_17") (pintype "bidirectional"))
      (node (ref "J1") (pin "8") (pinfunction "8_8") (pintype "bidirectional"))
      (node (ref "J1") (pin "MP1") (pinfunction "MP1_MP1") (pintype "bidirectional"))
      (node (ref "J1") (pin "MP2") (pinfunction "MP2_MP2") (pintype "bidirectional"))
      (node (ref "J2") (pin "3") (pinfunction "3_3") (pintype "bidirectional"))
      (node (ref "J2") (pin "5") (pinfunction "5_5") (pintype "bidirectional"))
      (node (ref "J4") (pin "A12_B1") (pinfunction "GND_A12_B1") (pintype "power_in"))
      (node (ref "J4") (pin "A1_B12") (pinfunction "GND_A1_B12") (pintype "power_in"))
      (node (ref "J4") (pin "SH1") (pinfunction "SHIELD_SH1") (pintype "passive"))
      (node (ref "J4") (pin "SH2") (pinfunction "SHIELD_SH2") (pintype "passive"))
      (node (ref "J4") (pin "SH3") (pinfunction "SHIELD_SH3") (pintype "passive"))
      (node (ref "J4") (pin "SH4") (pinfunction "SHIELD_SH4") (pintype "passive"))
      (node (ref "R1_USB") (pin "1") (pinfunction "1_1") (pintype "bidirectional"))
      (node (ref "R2_EP_DR") (pin "1") (pinfunction "1_1") (pintype "bidirectional"))
      (node (ref "R2_USB") (pin "2") (pinfunction "2_2") (pintype "bidirectional"))
      (node (ref "R3") (pin "1") (pinfunction "1_1") (pintype "bidirectional"))
      (node (ref "R9") (pin "1") (pinfunction "1_1") (pintype "bidirectional"))
      (node (ref "R_TYPE_SEL") (pin "1") (pinfunction "1_1") (pintype "bidirectional"))
      (node (ref "SJ1") (pin "1") (pinfunction "1_1") (pintype "passive"))
      (node (ref "SW_DN") (pin "1") (pinfunction "1_1") (pintype "passive"))
      (node (ref "SW_ENT") (pin "1") (pinfunction "1_1") (pintype "passive"))
      (node (ref "SW_UP") (pin "1") (pinfunction "1_1") (pintype "passive"))
      (node (ref "TP_BAT_GND") (pin "TP") (pinfunction "TP_TP") (pintype "input"))
      (node (ref "TP_GND") (pin "TP") (pinfunction "TP_TP") (pintype "input"))
      (node (ref "U1") (pin "P$74") (pinfunction "VSS_PAD_P$74") (pintype "bidirectional"))
      (node (ref "U1") (pin "P$75") (pinfunction "VSS_PAD_P$75") (pintype "bidirectional"))
      (node (ref "U1") (pin "P$76") (pinfunction "VSS_PAD_P$76") (pintype "bidirectional"))
      (node (ref "U1") (pin "P$77") (pinfunction "VSS_PAD_P$77") (pintype "bidirectional"))
      (node (ref "U1") (pin "P$78") (pinfunction "VSS_PAD_P$78") (pintype "bidirectional"))
      (node (ref "U1") (pin "P$79") (pinfunction "VSS_PAD_P$79") (pintype "bidirectional"))
      (node (ref "U1") (pin "P$80") (pinfunction "VSS_PAD_P$80") (pintype "bidirectional"))
      (node (ref "U1") (pin "P$81") (pinfunction "VSS_PAD_P$81") (pintype "bidirectional"))
      (node (ref "U1") (pin "P$82") (pinfunction "VSS_PAD_P$82") (pintype "bidirectional"))
      (node (ref "U1") (pin "P$83") (pinfunction "VSS_PAD_P$83") (pintype "bidirectional"))
      (node (ref "U1") (pin "P$84") (pinfunction "VSS_PAD_P$84") (pintype "bidirectional"))
      (node (ref "U1") (pin "P$85") (pinfunction "VSS_PAD_P$85") (pintype "bidirectional"))
      (node (ref "U1") (pin "P$86") (pinfunction "VSS_PAD_P$86") (pintype "bidirectional"))
      (node (ref "U1") (pin "P$87") (pinfunction "VSS_PAD_P$87") (pintype "bidirectional"))
      (node (ref "U1") (pin "P$88") (pinfunction "VSS_PAD_P$88") (pintype "bidirectional"))
      (node (ref "U1") (pin "P$89") (pinfunction "VSS_PAD_P$89") (pintype "bidirectional"))
      (node (ref "U1") (pin "P$90") (pinfunction "VSS_PAD_P$90") (pintype "bidirectional"))
      (node (ref "U1") (pin "P$B7") (pinfunction "VSS_P$B7") (pintype "power_in"))
      (node (ref "U1") (pin "P$F23") (pinfunction "VSS_PA_P$F23") (pintype "bidirectional"))
      (node (ref "U3") (pin "1") (pinfunction "CTG_1") (pintype "power_in"))
      (node (ref "U3") (pin "4") (pinfunction "GND_4") (pintype "power_in"))
      (node (ref "U3") (pin "6") (pinfunction "QSTRT_6") (pintype "input"))
      (node (ref "U3") (pin "9") (pinfunction "EP_9") (pintype "power_in"))
      (node (ref "X1") (pin "2") (pinfunction "2_2") (pintype "passive"))
      (node (ref "X1") (pin "4") (pinfunction "4_4") (pintype "passive"))
    )
    (net (code "15") (name "HAPTIC_EN") (class "Default")
      (node (ref "IC2") (pin "A1") (pinfunction "EN_A1") (pintype "bidirectional"))
      (node (ref "U1") (pin "P$U1") (pinfunction "P0.12_P$U1") (pintype "bidirectional"))
    )
    (net (code "16") (name "IMU_INT1") (class "Default")
      (node (ref "IC3") (pin "5") (pinfunction "INT1_5") (pintype "bidirectional"))
      (node (ref "U1") (pin "P$N1") (pinfunction "P0.08_P$N1") (pintype "bidirectional"))
    )
    (net (code "17") (name "IMU_INT2") (class "Default")
      (node (ref "IC3") (pin "6") (pinfunction "INT2_6") (pintype "bidirectional"))
      (node (ref "U1") (pin "P$P2") (pinfunction "P1.08_P$P2") (pintype "bidirectional"))
    )
    (net (code "18") (name "LX1") (class "Default")
      (node (ref "IC9") (pin "B2") (pinfunction "SW1_1_B2") (pintype "bidirectional"))
      (node (ref "IC9") (pin "B3") (pinfunction "SW1_2_B3") (pintype "bidirectional"))
      (node (ref "L7") (pin "1") (pinfunction "1_1") (pintype "bidirectional"))
    )
    (net (code "19") (name "LX2") (class "Default")
      (node (ref "IC9") (pin "D2") (pinfunction "SW2_1_D2") (pintype "bidirectional"))
      (node (ref "IC9") (pin "D3") (pinfunction "SW2_2_D3") (pintype "bidirectional"))
      (node (ref "L7") (pin "2") (pinfunction "2_2") (pintype "bidirectional"))
    )
    (net (code "20") (name "MOSI") (class "Default")
      (node (ref "J1") (pin "14") (pinfunction "14_14") (pintype "bidirectional"))
      (node (ref "U1") (pin "P$B13") (pinfunction "P0.03/AIN1_P$B13") (pintype "bidirectional"))
    )
    (net (code "21") (name "Net-(ANT1-FEED)") (class "Default")
      (node (ref "ANT1") (pin "1") (pinfunction "FEED_1") (pintype "input"))
      (node (ref "C22") (pin "1") (pinfunction "1_1") (pintype "passive"))
      (node (ref "C4") (pin "1") (pinfunction "1_1") (pintype "passive"))
      (node (ref "L1") (pin "2") (pinfunction "2_2") (pintype "passive"))
    )
    (net (code "22") (name "Net-(C12-Pad1)") (class "Default")
      (node (ref "C12") (pin "1") (pinfunction "1_1") (pintype "passive"))
      (node (ref "U1") (pin "P$A22") (pinfunction "VDD_P$A22") (pintype "power_in"))
    )
    (net (code "23") (name "Net-(D2-K)") (class "Default")
      (node (ref "C2-EP-DR") (pin "1") (pinfunction "1_1") (pintype "passive"))
      (node (ref "D2") (pin "1") (pinfunction "K_1") (pintype "bidirectional"))
      (node (ref "D4") (pin "2") (pinfunction "A_2") (pintype "bidirectional"))
    )
    (net (code "24") (name "Net-(D5-A)") (class "Default")
      (node (ref "C2-EP-DR") (pin "2") (pinfunction "2_2") (pintype "passive"))
      (node (ref "D5") (pin "2") (pinfunction "A_2") (pintype "bidirectional"))
      (node (ref "L5") (pin "1") (pinfunction "1_1") (pintype "passive"))
      (node (ref "Q3") (pin "3") (pinfunction "D_3") (pintype "bidirectional"))
    )
    (net (code "25") (name "Net-(EPD_C1-Pad2)") (class "Default")
      (node (ref "EPD_C1") (pin "2") (pinfunction "2_2") (pintype "passive"))
      (node (ref "J1") (pin "5") (pinfunction "5_5") (pintype "bidirectional"))
    )
    (net (code "26") (name "Net-(EPD_C2-Pad2)") (class "Default")
      (node (ref "EPD_C2") (pin "2") (pinfunction "2_2") (pintype "passive"))
      (node (ref "J1") (pin "4") (pinfunction "4_4") (pintype "bidirectional"))
    )
    (net (code "27") (name "Net-(EPD_C6-Pad2)") (class "Default")
      (node (ref "EPD_C6") (pin "2") (pinfunction "2_2") (pintype "passive"))
      (node (ref "J1") (pin "18") (pinfunction "18_18") (pintype "bidirectional"))
    )
    (net (code "28") (name "Net-(EPD_C7-Pad2)") (class "Default")
      (node (ref "EPD_C7") (pin "2") (pinfunction "2_2") (pintype "passive"))
      (node (ref "J1") (pin "19") (pinfunction "19_19") (pintype "bidirectional"))
    )
    (net (code "29") (name "Net-(EPD_C8-Pad2)") (class "Default")
      (node (ref "EPD_C8") (pin "2") (pinfunction "2_2") (pintype "passive"))
      (node (ref "J1") (pin "20") (pinfunction "20_20") (pintype "bidirectional"))
    )
    (net (code "30") (name "Net-(EPD_C10-Pad2)") (class "Default")
      (node (ref "EPD_C10") (pin "2") (pinfunction "2_2") (pintype "passive"))
      (node (ref "J1") (pin "22") (pinfunction "22_22") (pintype "bidirectional"))
    )
    (net (code "31") (name "Net-(EPD_C12-Pad2)") (class "Default")
      (node (ref "EPD_C12") (pin "2") (pinfunction "2_2") (pintype "passive"))
      (node (ref "J1") (pin "24") (pinfunction "24_24") (pintype "bidirectional"))
    )
    (net (code "32") (name "Net-(IC1-TS{slash}MR)") (class "Default")
      (node (ref "IC1") (pin "D1") (pinfunction "TS/MR_D1") (pintype "bidirectional"))
      (node (ref "R9") (pin "2") (pinfunction "2_2") (pintype "bidirectional"))
    )
    (net (code "33") (name "Net-(IC2-REG)") (class "Default")
      (node (ref "C32") (pin "2") (pinfunction "2_2") (pintype "passive"))
      (node (ref "IC2") (pin "A2") (pinfunction "REG_A2") (pintype "bidirectional"))
    )
    (net (code "34") (name "Net-(IC3-SDO)") (class "Default")
      (node (ref "IC3") (pin "1") (pinfunction "SDO_1") (pintype "bidirectional"))
      (node (ref "R3") (pin "2") (pinfunction "2_2") (pintype "bidirectional"))
    )
    (net (code "35") (name "Net-(IC9-SCL)") (class "Default")
      (node (ref "IC9") (pin "D1") (pinfunction "SCL_D1") (pintype "bidirectional"))
      (node (ref "R4") (pin "2") (pinfunction "2_2") (pintype "bidirectional"))
    )
    (net (code "36") (name "Net-(IC9-SDA)") (class "Default")
      (node (ref "IC9") (pin "E1") (pinfunction "SDA_E1") (pintype "bidirectional"))
      (node (ref "R2") (pin "2") (pinfunction "2_2") (pintype "bidirectional"))
    )
    (net (code "37") (name "Net-(J4-CC1)") (class "Default")
      (node (ref "J4") (pin "A5") (pinfunction "CC1_A5") (pintype "bidirectional"))
      (node (ref "R1_USB") (pin "2") (pinfunction "2_2") (pintype "bidirectional"))
    )
    (net (code "38") (name "Net-(J4-CC2)") (class "Default")
      (node (ref "J4") (pin "B5") (pinfunction "CC2_B5") (pintype "bidirectional"))
      (node (ref "R2_USB") (pin "1") (pinfunction "1_1") (pintype "bidirectional"))
    )
    (net (code "39") (name "Net-(L2-Pad2)") (class "Default")
      (node (ref "L2") (pin "2") (pinfunction "2_2") (pintype "passive"))
      (node (ref "L3") (pin "1") (pinfunction "1_1") (pintype "passive"))
    )
    (net (code "40") (name "Net-(R1_EP_DR-Pad1)") (class "Default")
      (node (ref "R1_EP_DR") (pin "1") (pinfunction "1_1") (pintype "bidirectional"))
      (node (ref "R_TYPE_SEL") (pin "2") (pinfunction "2_2") (pintype "bidirectional"))
      (node (ref "SJ1") (pin "2") (pinfunction "2_2") (pintype "passive"))
    )
    (net (code "41") (name "Net-(U1-ANT)") (class "Default")
      (node (ref "C3") (pin "1") (pinfunction "1_1") (pintype "passive"))
      (node (ref "L1") (pin "1") (pinfunction "1_1") (pintype "passive"))
      (node (ref "U1") (pin "P$H23") (pinfunction "ANT_P$H23") (pintype "bidirectional"))
    )
    (net (code "42") (name "Net-(U1-DCC)") (class "Default")
      (node (ref "L2") (pin "1") (pinfunction "1_1") (pintype "passive"))
      (node (ref "U1") (pin "P$B3") (pinfunction "DCC_P$B3") (pintype "output"))
    )
    (net (code "43") (name "Net-(U1-DEC1)") (class "Default")
      (node (ref "C5") (pin "1") (pinfunction "1_1") (pintype "passive"))
      (node (ref "U1") (pin "P$C1") (pinfunction "DEC1_P$C1") (pintype "power_in"))
    )
    (net (code "44") (name "Net-(U1-DEC2)") (class "Default")
      (node (ref "C13") (pin "1") (pinfunction "1_1") (pintype "passive"))
      (node (ref "U1") (pin "P$A18") (pinfunction "DEC2_P$A18") (pintype "bidirectional"))
    )
    (net (code "45") (name "Net-(U1-DEC3)") (class "Default")
      (node (ref "C11") (pin "1") (pinfunction "1_1") (pintype "passive"))
      (node (ref "U1") (pin "P$D23") (pinfunction "DEC3_P$D23") (pintype "bidirectional"))
    )
    (net (code "46") (name "Net-(U1-DEC3V3)") (class "Default")
      (node (ref "C20") (pin "1") (pinfunction "1_1") (pintype "passive"))
      (node (ref "U1") (pin "P$AC5") (pinfunction "DEC3V3_P$AC5") (pintype "bidirectional"))
    )
    (net (code "47") (name "Net-(U1-DEC5)") (class "Default")
      (node (ref "C9") (pin "1") (pinfunction "1_1") (pintype "passive"))
      (node (ref "U1") (pin "P$N24") (pinfunction "DEC5_P$N24") (pintype "bidirectional"))
    )
    (net (code "48") (name "Net-(U1-P0.00{slash}XL1)") (class "Default")
      (node (ref "C17") (pin "2") (pinfunction "2_2") (pintype "passive"))
      (node (ref "U1") (pin "P$D2") (pinfunction "P0.00/XL1_P$D2") (pintype "bidirectional"))
      (node (ref "X2") (pin "1") (pinfunction "1_1") (pintype "passive"))
    )
    (net (code "49") (name "Net-(U1-P0.01{slash}XL2)") (class "Default")
      (node (ref "C18") (pin "2") (pinfunction "2_2") (pintype "passive"))
      (node (ref "U1") (pin "P$F2") (pinfunction "P0.01/XL2_P$F2") (pintype "bidirectional"))
      (node (ref "X2") (pin "2") (pinfunction "2_2") (pintype "passive"))
    )
    (net (code "50") (name "Net-(U1-XC1)") (class "Default")
      (node (ref "C1") (pin "1") (pinfunction "1_1") (pintype "passive"))
      (node (ref "U1") (pin "P$B24") (pinfunction "XC1_P$B24") (pintype "input"))
      (node (ref "X1") (pin "1") (pinfunction "1_1") (pintype "passive"))
    )
    (net (code "51") (name "Net-(U1-XC2)") (class "Default")
      (node (ref "C2") (pin "1") (pinfunction "1_1") (pintype "passive"))
      (node (ref "U1") (pin "P$A23") (pinfunction "XC2_P$A23") (pintype "output"))
      (node (ref "X1") (pin "3") (pinfunction "3_3") (pintype "passive"))
    )
    (net (code "52") (name "OUT+") (class "Default")
      (node (ref "IC2") (pin "A3") (pinfunction "OUT+_A3") (pintype "bidirectional"))
      (node (ref "TP_OP") (pin "TP") (pinfunction "TP_TP") (pintype "input"))
    )
    (net (code "53") (name "OUT-") (class "Default")
      (node (ref "IC2") (pin "C3") (pinfunction "OUT-_C3") (pintype "bidirectional"))
      (node (ref "TP_ON") (pin "TP") (pinfunction "TP_TP") (pintype "input"))
    )
    (net (code "54") (name "P0.04") (class "Default")
      (node (ref "U1") (pin "P$J1") (pinfunction "P0.04/AIN2_P$J1") (pintype "bidirectional"))
    )
    (net (code "55") (name "P0.09") (class "Default")
      (node (ref "U1") (pin "P$L24") (pinfunction "P0.09/NFC1_P$L24") (pintype "bidirectional"))
    )
    (net (code "56") (name "P0.13") (class "Default")
      (node (ref "U1") (pin "P$AD8") (pinfunction "P0.13_P$AD8") (pintype "bidirectional"))
    )
    (net (code "57") (name "P0.14") (class "Default")
      (node (ref "U1") (pin "P$AC9") (pinfunction "P0.14_P$AC9") (pintype "bidirectional"))
    )
    (net (code "58") (name "P0.19") (class "Default")
      (node (ref "U1") (pin "P$AC15") (pinfunction "P0.19_P$AC15") (pintype "bidirectional"))
    )
    (net (code "59") (name "P0.20") (class "Default")
      (node (ref "U1") (pin "P$AD16") (pinfunction "P0.20_P$AD16") (pintype "bidirectional"))
    )
    (net (code "60") (name "P0.21") (class "Default")
      (node (ref "U1") (pin "P$AC17") (pinfunction "P0.21_P$AC17") (pintype "bidirectional"))
    )
    (net (code "61") (name "P0.22") (class "Default")
      (node (ref "U1") (pin "P$AD18") (pinfunction "P0.22_P$AD18") (pintype "bidirectional"))
    )
    (net (code "62") (name "P0.23") (class "Default")
      (node (ref "U1") (pin "P$AC19") (pinfunction "P0.23_P$AC19") (pintype "bidirectional"))
    )
    (net (code "63") (name "P0.24") (class "Default")
      (node (ref "U1") (pin "P$AD20") (pinfunction "P0.24_P$AD20") (pintype "bidirectional"))
    )
    (net (code "64") (name "P0.25") (class "Default")
      (node (ref "U1") (pin "P$AC21") (pinfunction "P0.25_P$AC21") (pintype "bidirectional"))
    )
    (net (code "65") (name "P0.26") (class "Default")
      (node (ref "U1") (pin "P$G1") (pinfunction "P0.26_P$G1") (pintype "bidirectional"))
    )
    (net (code "66") (name "P0.27") (class "Default")
      (node (ref "U1") (pin "P$H2") (pinfunction "P0.27_P$H2") (pintype "bidirectional"))
    )
    (net (code "67") (name "P0.28") (class "Default")
      (node (ref "U1") (pin "P$B11") (pinfunction "P0.28/AIN4_P$B11") (pintype "bidirectional"))
    )
    (net (code "68") (name "P0.29") (class "Default")
      (node (ref "U1") (pin "P$A10") (pinfunction "P0.29/AIN5_P$A10") (pintype "bidirectional"))
    )
    (net (code "69") (name "P0.30") (class "Default")
      (node (ref "U1") (pin "P$B9") (pinfunction "P0.30/AIN6_P$B9") (pintype "bidirectional"))
    )
    (net (code "70") (name "P0.31") (class "Default")
      (node (ref "U1") (pin "P$A8") (pinfunction "P0.31/AIN7_P$A8") (pintype "bidirectional"))
    )
    (net (code "71") (name "P1.01") (class "Default")
      (node (ref "Q1") (pin "1") (pinfunction "G_1") (pintype "bidirectional"))
      (node (ref "R_PWR_EPD") (pin "1") (pinfunction "1_1") (pintype "bidirectional"))
      (node (ref "U1") (pin "P$Y23") (pinfunction "P1.01_P$Y23") (pintype "bidirectional"))
    )
    (net (code "72") (name "P1.02") (class "Default")
      (node (ref "C29") (pin "2") (pinfunction "2_2") (pintype "passive"))
      (node (ref "C30") (pin "2") (pinfunction "2_2") (pintype "passive"))
      (node (ref "C31") (pin "2") (pinfunction "2_2") (pintype "passive"))
      (node (ref "R5") (pin "1") (pinfunction "1_1") (pintype "bidirectional"))
      (node (ref "R7") (pin "1") (pinfunction "1_1") (pintype "bidirectional"))
      (node (ref "R8") (pin "1") (pinfunction "1_1") (pintype "bidirectional"))
      (node (ref "SW_DN") (pin "2") (pinfunction "2_2") (pintype "passive"))
      (node (ref "SW_ENT") (pin "2") (pinfunction "2_2") (pintype "passive"))
      (node (ref "SW_UP") (pin "2") (pinfunction "2_2") (pintype "passive"))
      (node (ref "U1") (pin "P$W24") (pinfunction "P1.02_P$W24") (pintype "bidirectional"))
    )
    (net (code "73") (name "P1.03") (class "Default")
      (node (ref "U1") (pin "P$V23") (pinfunction "P1.03_P$V23") (pintype "bidirectional"))
    )
    (net (code "74") (name "P1.04") (class "Default")
      (node (ref "U1") (pin "P$U24") (pinfunction "P1.04_P$U24") (pintype "bidirectional"))
    )
    (net (code "75") (name "P1.05") (class "Default")
      (node (ref "U1") (pin "P$T23") (pinfunction "P1.05_P$T23") (pintype "bidirectional"))
    )
    (net (code "76") (name "P1.06") (class "Default")
      (node (ref "U1") (pin "P$R24") (pinfunction "P1.06_P$R24") (pintype "bidirectional"))
    )
    (net (code "77") (name "P1.07") (class "Default")
      (node (ref "U1") (pin "P$P23") (pinfunction "P1.07_P$P23") (pintype "bidirectional"))
    )
    (net (code "78") (name "P1.09") (class "Default")
      (node (ref "U1") (pin "P$R1") (pinfunction "P1.09_P$R1") (pintype "bidirectional"))
    )
    (net (code "79") (name "P1.10") (class "Default")
      (node (ref "U1") (pin "P$A20") (pinfunction "P1.10_P$A20") (pintype "bidirectional"))
    )
    (net (code "80") (name "P1.11") (class "Default")
      (node (ref "U1") (pin "P$B19") (pinfunction "P1.11_P$B19") (pintype "bidirectional"))
    )
    (net (code "81") (name "P1.12") (class "Default")
      (node (ref "U1") (pin "P$B17") (pinfunction "P1.12_P$B17") (pintype "bidirectional"))
    )
    (net (code "82") (name "P1.13") (class "Default")
      (node (ref "U1") (pin "P$A16") (pinfunction "P1.13_P$A16") (pintype "bidirectional"))
    )
    (net (code "83") (name "P1.14") (class "Default")
      (node (ref "U1") (pin "P$B15") (pinfunction "P1.14_P$B15") (pintype "bidirectional"))
    )
    (net (code "84") (name "P1.15") (class "Default")
      (node (ref "U1") (pin "P$A14") (pinfunction "P1.15_P$A14") (pintype "bidirectional"))
    )
    (net (code "85") (name "PMIC_INT") (class "Default")
      (node (ref "IC1") (pin "A1") (pinfunction "~{INT}_A1") (pintype "bidirectional"))
      (node (ref "U1") (pin "P$T2") (pinfunction "P0.11_P$T2") (pintype "bidirectional"))
    )
    (net (code "86") (name "PREVGH") (class "Default")
      (node (ref "D5") (pin "1") (pinfunction "K_1") (pintype "bidirectional"))
      (node (ref "EPD_C9") (pin "2") (pinfunction "2_2") (pintype "passive"))
      (node (ref "J1") (pin "21") (pinfunction "21_21") (pintype "bidirectional"))
    )
    (net (code "87") (name "PREVGL") (class "Default")
      (node (ref "D2") (pin "2") (pinfunction "A_2") (pintype "bidirectional"))
      (node (ref "EPD_C11") (pin "2") (pinfunction "2_2") (pintype "passive"))
      (node (ref "J1") (pin "23") (pinfunction "23_23") (pintype "bidirectional"))
    )
    (net (code "88") (name "RESE") (class "Default")
      (node (ref "J1") (pin "3") (pinfunction "3_3") (pintype "bidirectional"))
      (node (ref "Q3") (pin "2") (pinfunction "S_2") (pintype "bidirectional"))
      (node (ref "R1_EP_DR") (pin "2") (pinfunction "2_2") (pintype "bidirectional"))
    )
    (net (code "89") (name "RESET") (class "Default")
      (node (ref "J2") (pin "6") (pinfunction "6_6") (pintype "bidirectional"))
      (node (ref "TP_RESET") (pin "TP") (pinfunction "TP_TP") (pintype "input"))
      (node (ref "U1") (pin "P$AC13") (pinfunction "P0.18/RESET_P$AC13") (pintype "bidirectional"))
    )
    (net (code "90") (name "SCK") (class "Default")
      (node (ref "J1") (pin "13") (pinfunction "13_13") (pintype "bidirectional"))
      (node (ref "U1") (pin "P$A12") (pinfunction "P0.02/AIN0_P$A12") (pintype "bidirectional"))
    )
    (net (code "91") (name "SCL") (class "Default")
      (node (ref "IC1") (pin "B1") (pinfunction "SCL_B1") (pintype "bidirectional"))
      (node (ref "IC2") (pin "C1") (pinfunction "SCL_C1") (pintype "bidirectional"))
      (node (ref "IC3") (pin "12") (pinfunction "SCX_12") (pintype "bidirectional"))
      (node (ref "R17") (pin "2") (pinfunction "2_2") (pintype "bidirectional"))
      (node (ref "R4") (pin "1") (pinfunction "1_1") (pintype "bidirectional"))
      (node (ref "TP_SCL") (pin "TP") (pinfunction "TP_TP") (pintype "input"))
      (node (ref "U1") (pin "P$M2") (pinfunction "P0.07_P$M2") (pintype "bidirectional"))
      (node (ref "U3") (pin "7") (pinfunction "SCL_7") (pintype "input"))
    )
    (net (code "92") (name "SDA") (class "Default")
      (node (ref "IC1") (pin "C1") (pinfunction "SDA_C1") (pintype "bidirectional"))
      (node (ref "IC2") (pin "B2") (pinfunction "SDA_B2") (pintype "bidirectional"))
      (node (ref "IC3") (pin "2") (pinfunction "SDX_2") (pintype "bidirectional"))
      (node (ref "R18") (pin "2") (pinfunction "2_2") (pintype "bidirectional"))
      (node (ref "R2") (pin "1") (pinfunction "1_1") (pintype "bidirectional"))
      (node (ref "TP_SDA") (pin "TP") (pinfunction "TP_TP") (pintype "input"))
      (node (ref "U1") (pin "P$L1") (pinfunction "P0.06_P$L1") (pintype "bidirectional"))
      (node (ref "U3") (pin "8") (pinfunction "SDA_8") (pintype "bidirectional"))
    )
    (net (code "93") (name "SWDCLK") (class "Default")
      (node (ref "J2") (pin "4") (pinfunction "4_4") (pintype "bidirectional"))
      (node (ref "TP_SWDCLK") (pin "TP") (pinfunction "TP_TP") (pintype "input"))
      (node (ref "U1") (pin "P$AA24") (pinfunction "SWDCLK_P$AA24") (pintype "input"))
    )
    (net (code "94") (name "SWDIO") (class "Default")
      (node (ref "J2") (pin "2") (pinfunction "2_2") (pintype "bidirectional"))
      (node (ref "TP_SWDIO") (pin "TP") (pinfunction "TP_TP") (pintype "input"))
      (node (ref "U1") (pin "P$AC24") (pinfunction "SWDIO_P$AC24") (pintype "bidirectional"))
    )
    (net (code "95") (name "SWO") (class "Default")
      (node (ref "TP_SWO") (pin "TP") (pinfunction "TP_TP") (pintype "input"))
      (node (ref "U1") (pin "P$AD22") (pinfunction "P1.00_P$AD22") (pintype "bidirectional"))
    )
    (net (code "96") (name "VBAT") (class "Default")
      (node (ref "C27") (pin "2") (pinfunction "2_2") (pintype "passive"))
      (node (ref "C37") (pin "2") (pinfunction "2_2") (pintype "passive"))
      (node (ref "IC1") (pin "C2") (pinfunction "BAT_C2") (pintype "bidirectional"))
      (node (ref "TP_VBAT") (pin "TP") (pinfunction "TP_TP") (pintype "input"))
      (node (ref "U3") (pin "2") (pinfunction "CELL_2") (pintype "power_in"))
      (node (ref "U3") (pin "3") (pinfunction "VDD_3") (pintype "power_in"))
    )
    (net (code "97") (name "VBUS") (class "Default")
      (node (ref "C21") (pin "1") (pinfunction "1_1") (pintype "passive"))
      (node (ref "C38") (pin "2") (pinfunction "2_2") (pintype "passive"))
      (node (ref "C42") (pin "1") (pinfunction "1_1") (pintype "passive"))
      (node (ref "C43") (pin "1") (pinfunction "1_1") (pintype "passive"))
      (node (ref "D3") (pin "5") (pinfunction "VBUS_5") (pintype "bidirectional"))
      (node (ref "IC1") (pin "A2") (pinfunction "IN_A2") (pintype "bidirectional"))
      (node (ref "J4") (pin "A4_B9") (pinfunction "VBUS_A4_B9") (pintype "power_in"))
      (node (ref "J4") (pin "A9_B4") (pinfunction "VBUS_A9_B4") (pintype "power_in"))
      (node (ref "U1") (pin "P$AD2") (pinfunction "VBUS_P$AD2") (pintype "power_in"))
    )
    (net (code "98") (name "VREG") (class "Default")
      (node (ref "C23") (pin "2") (pinfunction "2_2") (pintype "passive"))
      (node (ref "C24") (pin "2") (pinfunction "2_2") (pintype "passive"))
      (node (ref "C39") (pin "1") (pinfunction "1_1") (pintype "passive"))
      (node (ref "IC1") (pin "B2") (pinfunction "SYS_B2") (pintype "bidirectional"))
      (node (ref "IC9") (pin "A1") (pinfunction "EN_A1") (pintype "bidirectional"))
      (node (ref "IC9") (pin "A2") (pinfunction "VIN_1_A2") (pintype "bidirectional"))
      (node (ref "IC9") (pin "A3") (pinfunction "VIN_2_A3") (pintype "bidirectional"))
      (node (ref "TP_VREG") (pin "TP") (pinfunction "TP_TP") (pintype "input"))
    )
    (net (code "99") (name "unconnected-(ANT1-NC-Pad2)") (class "Default")
      (node (ref "ANT1") (pin "2") (pinfunction "NC_2") (pintype "no_connect"))
    )
    (net (code "100") (name "unconnected-(IC3-ASCL-Pad11)") (class "Default")
      (node (ref "IC3") (pin "11") (pinfunction "ASCL_11") (pintype "bidirectional"))
    )
    (net (code "101") (name "unconnected-(IC3-ASDA-Pad4)") (class "Default")
      (node (ref "IC3") (pin "4") (pinfunction "ASDA_4") (pintype "bidirectional"))
    )
    (net (code "102") (name "unconnected-(J1-Pad1)") (class "Default")
      (node (ref "J1") (pin "1") (pinfunction "1_1") (pintype "bidirectional"))
    )
    (net (code "103") (name "unconnected-(J1-Pad6)") (class "Default")
      (node (ref "J1") (pin "6") (pinfunction "6_6") (pintype "bidirectional"))
    )
    (net (code "104") (name "unconnected-(J1-Pad7)") (class "Default")
      (node (ref "J1") (pin "7") (pinfunction "7_7") (pintype "bidirectional"))
    )
    (net (code "105") (name "unconnected-(J4-SBU1-PadA8)") (class "Default")
      (node (ref "J4") (pin "A8") (pinfunction "SBU1_A8") (pintype "bidirectional"))
    )
    (net (code "106") (name "unconnected-(J4-SBU2-PadB8)") (class "Default")
      (node (ref "J4") (pin "B8") (pinfunction "SBU2_B8") (pintype "bidirectional"))
    )
    (net (code "107") (name "unconnected-(U1-DCCH-PadP$AB2)") (class "Default")
      (node (ref "U1") (pin "P$AB2") (pinfunction "DCCH_P$AB2") (pintype "bidirectional"))
    )
  )
)
